# SCH_Badur_Gaddi_v0_1_5.net
KiCad netlist of a schematic drawn in EasyEDA
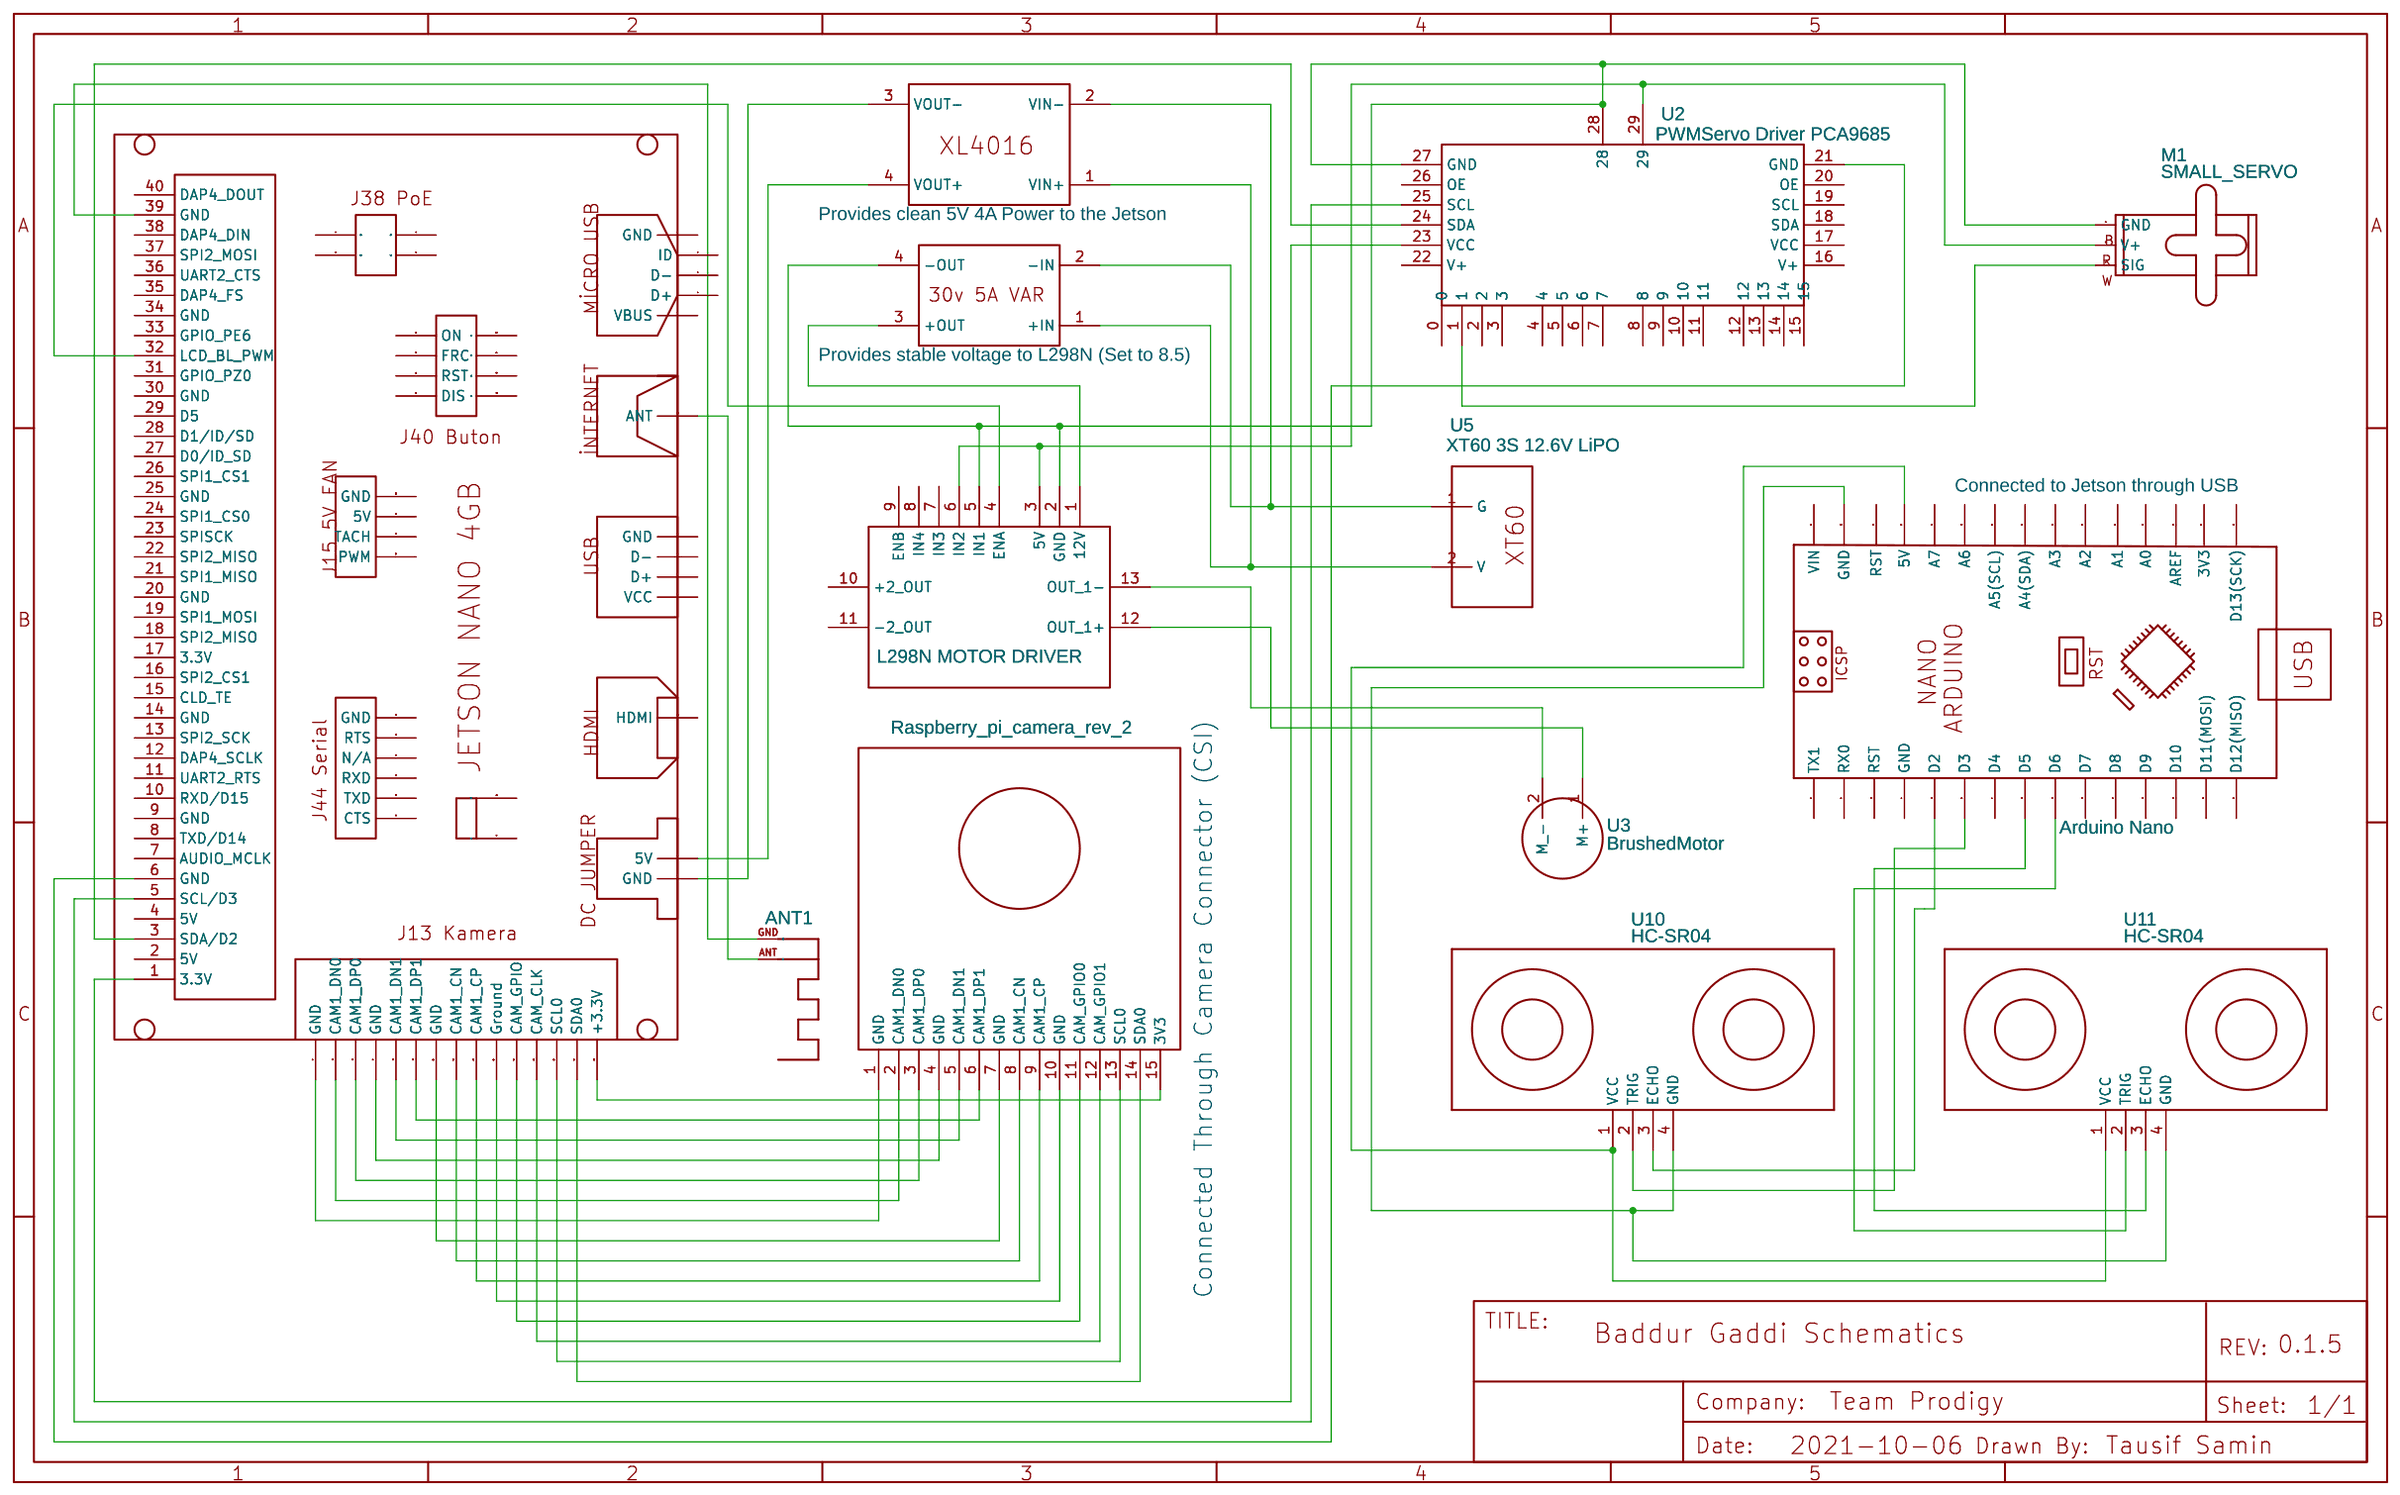
[diagram p0: schematic sheet]

(export (version "E")
  (design (tool "Eeschema 10.0.6"))
  (components
    (comp (ref "ANT1") (value "ANTENNA_WIFI_MIFA") (libsource (lib "") (part "ANTENNA_WIFI_MIFA")))
    (comp (ref "M1") (value "SMALL_SERVO") (libsource (lib "") (part "SMALL_SERVO")))
    (comp (ref "MODULE1") (value "L298N MOTOR DRIVER") (libsource (lib "") (part "L298N MOTOR DRIVER N")))
    (comp (ref "U1") (value "XL4016") (libsource (lib "") (part "XL4016")))
    (comp (ref "U2")
      (value "PWMServo Driver PCA9685")
      (fields
        (field (name "BOM_Manufacturer Part") "815")
        (field (name "BOM_Supplier Part") "16-Channel 12-bit PWMServo Driver PCA9685")
      )
      (libsource (lib "") (part "PWMServo Driver PCA9685"))
    )
    (comp (ref "U3") (value "BrushedMotor") (libsource (lib "") (part "BrushedMotor")))
    (comp (ref "U4") (value "Arduino Nano") (libsource (lib "") (part "Arduino Nano")))
    (comp (ref "U5") (value "XT60 3S 12.6V LiPO") (libsource (lib "") (part "XT60")))
    (comp (ref "U6") (value "jetson nano") (libsource (lib "") (part "jetson nano")))
    (comp (ref "U7")
      (value "Raspberry_pi_camera_rev_2")
      (libsource (lib "") (part "Raspberry_pi_camera_rev_1.3"))
    )
    (comp (ref "U9")
      (value "XL4015 PS 5A")
      (fields (field (name "BOM_Supplier Part") "XL4005"))
      (libsource (lib "") (part "XL4015 PS 5A"))
    )
    (comp (ref "U10") (value "HC-SR04") (libsource (lib "") (part "HC-SR04")))
    (comp (ref "U11") (value "HC-SR04") (libsource (lib "") (part "HC-SR04")))
  )
  (nets
    (net (code "1") (name "Net-(ANT1-PadGND)") (class "Default")
      (node (ref "ANT1") (pin "GND") (pinfunction "GND_GND") (pintype "unspecified"))
      (node (ref "U6") (pin "39") (pinfunction "GND_39") (pintype "unspecified"))
    )
    (net (code "2") (name "Net-(M1-GND)") (class "Default")
      (node (ref "M1") (pin "3") (pinfunction "GND_3") (pintype "unspecified"))
      (node (ref "MODULE1") (pin "2") (pinfunction "GND_2") (pintype "passive"))
      (node (ref "MODULE1") (pin "5") (pinfunction "IN1_5") (pintype "input"))
      (node (ref "U2") (pin "27") (pinfunction "GND_27") (pintype "unspecified"))
      (node (ref "U2") (pin "28") (pinfunction "28_28") (pintype "unspecified"))
      (node (ref "U9") (pin "4") (pinfunction "-OUT_4") (pintype "unspecified"))
    )
    (net (code "3") (name "Net-(M1-SIG)") (class "Default")
      (node (ref "M1") (pin "1") (pinfunction "SIG_1") (pintype "unspecified"))
      (node (ref "U2") (pin "1") (pinfunction "1_1") (pintype "unspecified"))
    )
    (net (code "4") (name "Net-(M1-V+)") (class "Default")
      (node (ref "M1") (pin "2") (pinfunction "V+_2") (pintype "unspecified"))
      (node (ref "MODULE1") (pin "3") (pinfunction "5V_3") (pintype "passive"))
      (node (ref "MODULE1") (pin "6") (pinfunction "IN2_6") (pintype "input"))
      (node (ref "U2") (pin "29") (pinfunction "29_29") (pintype "unspecified"))
    )
    (net (code "5") (name "Net-(MODULE1-12V)") (class "Default")
      (node (ref "MODULE1") (pin "1") (pinfunction "12V_1") (pintype "passive"))
      (node (ref "U9") (pin "3") (pinfunction "+OUT_3") (pintype "unspecified"))
    )
    (net (code "6") (name "Net-(MODULE1-ENA)") (class "Default")
      (node (ref "MODULE1") (pin "4") (pinfunction "ENA_4") (pintype "input"))
      (node (ref "U6") (pin "32") (pinfunction "LCD_BL_PWM_32") (pintype "unspecified"))
    )
    (net (code "7") (name "Net-(MODULE1-OUT_1+)") (class "Default")
      (node (ref "MODULE1") (pin "12") (pinfunction "OUT_1+_12") (pintype "output"))
      (node (ref "U3") (pin "1") (pinfunction "M+_1") (pintype "unspecified"))
    )
    (net (code "8") (name "Net-(MODULE1-OUT_1-)") (class "Default")
      (node (ref "MODULE1") (pin "13") (pinfunction "OUT_1-_13") (pintype "output"))
      (node (ref "U3") (pin "2") (pinfunction "M_-_2") (pintype "unspecified"))
    )
    (net (code "9") (name "Net-(U1-VIN+)") (class "Default")
      (node (ref "U1") (pin "1") (pinfunction "VIN+_1") (pintype "unspecified"))
      (node (ref "U5") (pin "2") (pinfunction "V_2") (pintype "unspecified"))
      (node (ref "U9") (pin "1") (pinfunction "+IN_1") (pintype "unspecified"))
    )
    (net (code "10") (name "Net-(U1-VIN-)") (class "Default")
      (node (ref "U1") (pin "2") (pinfunction "VIN-_2") (pintype "unspecified"))
      (node (ref "U5") (pin "1") (pinfunction "G_1") (pintype "unspecified"))
      (node (ref "U9") (pin "2") (pinfunction "-IN_2") (pintype "unspecified"))
    )
    (net (code "11") (name "Net-(U1-VOUT+)") (class "Default")
      (node (ref "U1") (pin "4") (pinfunction "VOUT+_4") (pintype "unspecified"))
      (node (ref "U6") (pin "62") (pinfunction "5V_62") (pintype "unspecified"))
    )
    (net (code "12") (name "Net-(U1-VOUT-)") (class "Default")
      (node (ref "U1") (pin "3") (pinfunction "VOUT-_3") (pintype "unspecified"))
      (node (ref "U6") (pin "61") (pinfunction "GND_61") (pintype "unspecified"))
    )
    (net (code "13") (name "Net-(U2-GND-Pad21)") (class "Default")
      (node (ref "U2") (pin "21") (pinfunction "GND_21") (pintype "unspecified"))
      (node (ref "U6") (pin "6") (pinfunction "GND_6") (pintype "unspecified"))
    )
    (net (code "14") (name "Net-(U2-VCC-Pad23)") (class "Default")
      (node (ref "U2") (pin "23") (pinfunction "VCC_23") (pintype "unspecified"))
      (node (ref "U6") (pin "1") (pinfunction "3.3V_1") (pintype "unspecified"))
    )
    (net (code "15") (name "Net-(U6-+3.3V)") (class "Default")
      (node (ref "U6") (pin "88") (pinfunction "+3.3V_88") (pintype "unspecified"))
      (node (ref "U7") (pin "15") (pinfunction "3V3_15") (pintype "unspecified"))
    )
    (net (code "16") (name "Net-(U6-ANT)") (class "Default")
      (node (ref "ANT1") (pin "ANT") (pinfunction "ANT_ANT") (pintype "unspecified"))
      (node (ref "U6") (pin "ETHERNET") (pinfunction "ANT_ETHERNET") (pintype "unspecified"))
    )
    (net (code "17") (name "Net-(U6-CAM1_CN)") (class "Default")
      (node (ref "U6") (pin "81") (pinfunction "CAM1_CN_81") (pintype "unspecified"))
      (node (ref "U7") (pin "8") (pinfunction "CAM1_CN_8") (pintype "unspecified"))
    )
    (net (code "18") (name "Net-(U6-CAM1_CP)") (class "Default")
      (node (ref "U6") (pin "82") (pinfunction "CAM1_CP_82") (pintype "unspecified"))
      (node (ref "U7") (pin "9") (pinfunction "CAM1_CP_9") (pintype "unspecified"))
    )
    (net (code "19") (name "Net-(U6-CAM1_DN0)") (class "Default")
      (node (ref "U6") (pin "75") (pinfunction "CAM1_DN0_75") (pintype "unspecified"))
      (node (ref "U7") (pin "2") (pinfunction "CAM1_DN0_2") (pintype "unspecified"))
    )
    (net (code "20") (name "Net-(U6-CAM1_DN1)") (class "Default")
      (node (ref "U6") (pin "78") (pinfunction "CAM1_DN1_78") (pintype "unspecified"))
      (node (ref "U7") (pin "5") (pinfunction "CAM1_DN1_5") (pintype "unspecified"))
    )
    (net (code "21") (name "Net-(U6-CAM1_DP0)") (class "Default")
      (node (ref "U6") (pin "76") (pinfunction "CAM1_DP0_76") (pintype "unspecified"))
      (node (ref "U7") (pin "3") (pinfunction "CAM1_DP0_3") (pintype "unspecified"))
    )
    (net (code "22") (name "Net-(U6-CAM1_DP1)") (class "Default")
      (node (ref "U6") (pin "79") (pinfunction "CAM1_DP1_79") (pintype "unspecified"))
      (node (ref "U7") (pin "6") (pinfunction "CAM1_DP1_6") (pintype "unspecified"))
    )
    (net (code "23") (name "Net-(U6-CAM_CLK)") (class "Default")
      (node (ref "U6") (pin "85") (pinfunction "CAM_CLK_85") (pintype "unspecified"))
      (node (ref "U7") (pin "12") (pinfunction "CAM_GPIO1_12") (pintype "unspecified"))
    )
    (net (code "24") (name "Net-(U6-CAM_GPIO)") (class "Default")
      (node (ref "U6") (pin "84") (pinfunction "CAM_GPIO_84") (pintype "unspecified"))
      (node (ref "U7") (pin "11") (pinfunction "CAM_GPIO0_11") (pintype "unspecified"))
    )
    (net (code "25") (name "Net-(U6-GND-Pad74)") (class "Default")
      (node (ref "U6") (pin "74") (pinfunction "GND_74") (pintype "unspecified"))
      (node (ref "U7") (pin "1") (pinfunction "GND_1") (pintype "unspecified"))
    )
    (net (code "26") (name "Net-(U6-GND-Pad77)") (class "Default")
      (node (ref "U6") (pin "77") (pinfunction "GND_77") (pintype "unspecified"))
      (node (ref "U7") (pin "4") (pinfunction "GND_4") (pintype "unspecified"))
    )
    (net (code "27") (name "Net-(U6-GND-Pad80)") (class "Default")
      (node (ref "U6") (pin "80") (pinfunction "GND_80") (pintype "unspecified"))
      (node (ref "U7") (pin "7") (pinfunction "GND_7") (pintype "unspecified"))
    )
    (net (code "28") (name "Net-(U6-Ground)") (class "Default")
      (node (ref "U6") (pin "83") (pinfunction "Ground_83") (pintype "unspecified"))
      (node (ref "U7") (pin "10") (pinfunction "GND_10") (pintype "unspecified"))
    )
    (net (code "29") (name "Net-(U6-SCL0)") (class "Default")
      (node (ref "U6") (pin "86") (pinfunction "SCL0_86") (pintype "unspecified"))
      (node (ref "U7") (pin "13") (pinfunction "SCL0_13") (pintype "unspecified"))
    )
    (net (code "30") (name "Net-(U6-SCL{slash}D3)") (class "Default")
      (node (ref "U2") (pin "25") (pinfunction "SCL_25") (pintype "unspecified"))
      (node (ref "U6") (pin "5") (pinfunction "SCL/D3_5") (pintype "unspecified"))
    )
    (net (code "31") (name "Net-(U6-SDA0)") (class "Default")
      (node (ref "U6") (pin "87") (pinfunction "SDA0_87") (pintype "unspecified"))
      (node (ref "U7") (pin "14") (pinfunction "SDA0_14") (pintype "unspecified"))
    )
    (net (code "32") (name "Net-(U6-SDA{slash}D2)") (class "Default")
      (node (ref "U2") (pin "24") (pinfunction "SDA_24") (pintype "unspecified"))
      (node (ref "U6") (pin "3") (pinfunction "SDA/D2_3") (pintype "unspecified"))
    )
    (net (code "33") (name "Net-(U10-ECHO)") (class "Default")
      (node (ref "U10") (pin "3") (pinfunction "ECHO_3") (pintype "output"))
      (node (ref "U4") (pin "5") (pinfunction "D2_5") (pintype "unspecified"))
    )
    (net (code "34") (name "Net-(U10-GND)") (class "Default")
      (node (ref "U10") (pin "4") (pinfunction "GND_4") (pintype "passive"))
      (node (ref "U11") (pin "4") (pinfunction "GND_4") (pintype "passive"))
      (node (ref "U4") (pin "29") (pinfunction "GND_29") (pintype "unspecified"))
    )
    (net (code "35") (name "Net-(U10-TRIG)") (class "Default")
      (node (ref "U10") (pin "2") (pinfunction "TRIG_2") (pintype "input"))
      (node (ref "U4") (pin "6") (pinfunction "D3_6") (pintype "unspecified"))
    )
    (net (code "36") (name "Net-(U10-VCC)") (class "Default")
      (node (ref "U10") (pin "1") (pinfunction "VCC_1") (pintype "passive"))
      (node (ref "U11") (pin "1") (pinfunction "VCC_1") (pintype "passive"))
      (node (ref "U4") (pin "27") (pinfunction "5V_27") (pintype "unspecified"))
    )
    (net (code "37") (name "Net-(U11-ECHO)") (class "Default")
      (node (ref "U11") (pin "3") (pinfunction "ECHO_3") (pintype "output"))
      (node (ref "U4") (pin "8") (pinfunction "D5_8") (pintype "unspecified"))
    )
    (net (code "38") (name "Net-(U11-TRIG)") (class "Default")
      (node (ref "U11") (pin "2") (pinfunction "TRIG_2") (pintype "input"))
      (node (ref "U4") (pin "9") (pinfunction "D6_9") (pintype "unspecified"))
    )
    (net (code "39") (name "unconnected-(MODULE1-+2_OUT-Pad10)") (class "Default")
      (node (ref "MODULE1") (pin "10") (pinfunction "+2_OUT_10") (pintype "output"))
    )
    (net (code "40") (name "unconnected-(MODULE1--2_OUT-Pad11)") (class "Default")
      (node (ref "MODULE1") (pin "11") (pinfunction "-2_OUT_11") (pintype "output"))
    )
    (net (code "41") (name "unconnected-(MODULE1-ENB-Pad9)") (class "Default")
      (node (ref "MODULE1") (pin "9") (pinfunction "ENB_9") (pintype "input"))
    )
    (net (code "42") (name "unconnected-(MODULE1-IN3-Pad7)") (class "Default")
      (node (ref "MODULE1") (pin "7") (pinfunction "IN3_7") (pintype "input"))
    )
    (net (code "43") (name "unconnected-(MODULE1-IN4-Pad8)") (class "Default")
      (node (ref "MODULE1") (pin "8") (pinfunction "IN4_8") (pintype "input"))
    )
    (net (code "44") (name "unconnected-(U2-OE-Pad20)") (class "Default")
      (node (ref "U2") (pin "20") (pinfunction "OE_20") (pintype "unspecified"))
    )
    (net (code "45") (name "unconnected-(U2-OE-Pad26)") (class "Default")
      (node (ref "U2") (pin "26") (pinfunction "OE_26") (pintype "unspecified"))
    )
    (net (code "46") (name "unconnected-(U2-Pad0)") (class "Default")
      (node (ref "U2") (pin "0") (pinfunction "0_0") (pintype "unspecified"))
    )
    (net (code "47") (name "unconnected-(U2-Pad2)") (class "Default")
      (node (ref "U2") (pin "2") (pinfunction "2_2") (pintype "unspecified"))
    )
    (net (code "48") (name "unconnected-(U2-Pad3)") (class "Default")
      (node (ref "U2") (pin "3") (pinfunction "3_3") (pintype "unspecified"))
    )
    (net (code "49") (name "unconnected-(U2-Pad4)") (class "Default")
      (node (ref "U2") (pin "4") (pinfunction "4_4") (pintype "unspecified"))
    )
    (net (code "50") (name "unconnected-(U2-Pad5)") (class "Default")
      (node (ref "U2") (pin "5") (pinfunction "5_5") (pintype "unspecified"))
    )
    (net (code "51") (name "unconnected-(U2-Pad6)") (class "Default")
      (node (ref "U2") (pin "6") (pinfunction "6_6") (pintype "unspecified"))
    )
    (net (code "52") (name "unconnected-(U2-Pad7)") (class "Default")
      (node (ref "U2") (pin "7") (pinfunction "7_7") (pintype "unspecified"))
    )
    (net (code "53") (name "unconnected-(U2-Pad8)") (class "Default")
      (node (ref "U2") (pin "8") (pinfunction "8_8") (pintype "unspecified"))
    )
    (net (code "54") (name "unconnected-(U2-Pad9)") (class "Default")
      (node (ref "U2") (pin "9") (pinfunction "9_9") (pintype "unspecified"))
    )
    (net (code "55") (name "unconnected-(U2-Pad10)") (class "Default")
      (node (ref "U2") (pin "10") (pinfunction "10_10") (pintype "unspecified"))
    )
    (net (code "56") (name "unconnected-(U2-Pad11)") (class "Default")
      (node (ref "U2") (pin "11") (pinfunction "11_11") (pintype "unspecified"))
    )
    (net (code "57") (name "unconnected-(U2-Pad12)") (class "Default")
      (node (ref "U2") (pin "12") (pinfunction "12_12") (pintype "unspecified"))
    )
    (net (code "58") (name "unconnected-(U2-Pad13)") (class "Default")
      (node (ref "U2") (pin "13") (pinfunction "13_13") (pintype "unspecified"))
    )
    (net (code "59") (name "unconnected-(U2-Pad14)") (class "Default")
      (node (ref "U2") (pin "14") (pinfunction "14_14") (pintype "unspecified"))
    )
    (net (code "60") (name "unconnected-(U2-Pad15)") (class "Default")
      (node (ref "U2") (pin "15") (pinfunction "15_15") (pintype "unspecified"))
    )
    (net (code "61") (name "unconnected-(U2-SCL-Pad19)") (class "Default")
      (node (ref "U2") (pin "19") (pinfunction "SCL_19") (pintype "unspecified"))
    )
    (net (code "62") (name "unconnected-(U2-SDA-Pad18)") (class "Default")
      (node (ref "U2") (pin "18") (pinfunction "SDA_18") (pintype "unspecified"))
    )
    (net (code "63") (name "unconnected-(U2-V+-Pad16)") (class "Default")
      (node (ref "U2") (pin "16") (pinfunction "V+_16") (pintype "unspecified"))
    )
    (net (code "64") (name "unconnected-(U2-V+-Pad22)") (class "Default")
      (node (ref "U2") (pin "22") (pinfunction "V+_22") (pintype "unspecified"))
    )
    (net (code "65") (name "unconnected-(U2-VCC-Pad17)") (class "Default")
      (node (ref "U2") (pin "17") (pinfunction "VCC_17") (pintype "unspecified"))
    )
    (net (code "66") (name "unconnected-(U4-3V3-Pad17)") (class "Default")
      (node (ref "U4") (pin "17") (pinfunction "3V3_17") (pintype "unspecified"))
    )
    (net (code "67") (name "unconnected-(U4-A0-Pad19)") (class "Default")
      (node (ref "U4") (pin "19") (pinfunction "A0_19") (pintype "unspecified"))
    )
    (net (code "68") (name "unconnected-(U4-A1-Pad20)") (class "Default")
      (node (ref "U4") (pin "20") (pinfunction "A1_20") (pintype "unspecified"))
    )
    (net (code "69") (name "unconnected-(U4-A2-Pad21)") (class "Default")
      (node (ref "U4") (pin "21") (pinfunction "A2_21") (pintype "unspecified"))
    )
    (net (code "70") (name "unconnected-(U4-A3-Pad22)") (class "Default")
      (node (ref "U4") (pin "22") (pinfunction "A3_22") (pintype "unspecified"))
    )
    (net (code "71") (name "unconnected-(U4-A4(SDA)-Pad23)") (class "Default")
      (node (ref "U4") (pin "23") (pinfunction "A4(SDA)_23") (pintype "unspecified"))
    )
    (net (code "72") (name "unconnected-(U4-A5(SCL)-Pad24)") (class "Default")
      (node (ref "U4") (pin "24") (pinfunction "A5(SCL)_24") (pintype "unspecified"))
    )
    (net (code "73") (name "unconnected-(U4-A6-Pad25)") (class "Default")
      (node (ref "U4") (pin "25") (pinfunction "A6_25") (pintype "unspecified"))
    )
    (net (code "74") (name "unconnected-(U4-A7-Pad26)") (class "Default")
      (node (ref "U4") (pin "26") (pinfunction "A7_26") (pintype "unspecified"))
    )
    (net (code "75") (name "unconnected-(U4-AREF-Pad18)") (class "Default")
      (node (ref "U4") (pin "18") (pinfunction "AREF_18") (pintype "unspecified"))
    )
    (net (code "76") (name "unconnected-(U4-D4-Pad7)") (class "Default")
      (node (ref "U4") (pin "7") (pinfunction "D4_7") (pintype "unspecified"))
    )
    (net (code "77") (name "unconnected-(U4-D7-Pad10)") (class "Default")
      (node (ref "U4") (pin "10") (pinfunction "D7_10") (pintype "unspecified"))
    )
    (net (code "78") (name "unconnected-(U4-D8-Pad11)") (class "Default")
      (node (ref "U4") (pin "11") (pinfunction "D8_11") (pintype "unspecified"))
    )
    (net (code "79") (name "unconnected-(U4-D9-Pad12)") (class "Default")
      (node (ref "U4") (pin "12") (pinfunction "D9_12") (pintype "unspecified"))
    )
    (net (code "80") (name "unconnected-(U4-D10-Pad13)") (class "Default")
      (node (ref "U4") (pin "13") (pinfunction "D10_13") (pintype "unspecified"))
    )
    (net (code "81") (name "unconnected-(U4-D11(MOSI)-Pad14)") (class "Default")
      (node (ref "U4") (pin "14") (pinfunction "D11(MOSI)_14") (pintype "unspecified"))
    )
    (net (code "82") (name "unconnected-(U4-D12(MISO)-Pad15)") (class "Default")
      (node (ref "U4") (pin "15") (pinfunction "D12(MISO)_15") (pintype "unspecified"))
    )
    (net (code "83") (name "unconnected-(U4-D13(SCK)-Pad16)") (class "Default")
      (node (ref "U4") (pin "16") (pinfunction "D13(SCK)_16") (pintype "unspecified"))
    )
    (net (code "84") (name "unconnected-(U4-GND-Pad4)") (class "Default")
      (node (ref "U4") (pin "4") (pinfunction "GND_4") (pintype "unspecified"))
    )
    (net (code "85") (name "unconnected-(U4-RST-Pad3)") (class "Default")
      (node (ref "U4") (pin "3") (pinfunction "RST_3") (pintype "unspecified"))
    )
    (net (code "86") (name "unconnected-(U4-RST-Pad28)") (class "Default")
      (node (ref "U4") (pin "28") (pinfunction "RST_28") (pintype "unspecified"))
    )
    (net (code "87") (name "unconnected-(U4-RX0-Pad2)") (class "Default")
      (node (ref "U4") (pin "2") (pinfunction "RX0_2") (pintype "unspecified"))
    )
    (net (code "88") (name "unconnected-(U4-TX1-Pad1)") (class "Default")
      (node (ref "U4") (pin "1") (pinfunction "TX1_1") (pintype "unspecified"))
    )
    (net (code "89") (name "unconnected-(U4-VIN-Pad30)") (class "Default")
      (node (ref "U4") (pin "30") (pinfunction "VIN_30") (pintype "unspecified"))
    )
    (net (code "90") (name "unconnected-(U6-3.3V-Pad17)") (class "Default")
      (node (ref "U6") (pin "17") (pinfunction "3.3V_17") (pintype "unspecified"))
    )
    (net (code "91") (name "unconnected-(U6-5V-Pad2)") (class "Default")
      (node (ref "U6") (pin "2") (pinfunction "5V_2") (pintype "unspecified"))
    )
    (net (code "92") (name "unconnected-(U6-5V-Pad4)") (class "Default")
      (node (ref "U6") (pin "4") (pinfunction "5V_4") (pintype "unspecified"))
    )
    (net (code "93") (name "unconnected-(U6-5V-Pad59)") (class "Default")
      (node (ref "U6") (pin "59") (pinfunction "5V_59") (pintype "unspecified"))
    )
    (net (code "94") (name "unconnected-(U6-AUDIO_MCLK-Pad7)") (class "Default")
      (node (ref "U6") (pin "7") (pinfunction "AUDIO_MCLK_7") (pintype "unspecified"))
    )
    (net (code "95") (name "unconnected-(U6-CLD_TE-Pad15)") (class "Default")
      (node (ref "U6") (pin "15") (pinfunction "CLD_TE_15") (pintype "unspecified"))
    )
    (net (code "96") (name "unconnected-(U6-CTS-Pad41)") (class "Default")
      (node (ref "U6") (pin "41") (pinfunction "CTS_41") (pintype "unspecified"))
    )
    (net (code "97") (name "unconnected-(U6-D+-Pad.)") (class "Default")
      (node (ref "U6") (pin ".") (pinfunction "D+_.") (pintype "unspecified"))
    )
    (net (code "98") (name "unconnected-(U6-D+-Pad71)") (class "Default")
      (node (ref "U6") (pin "71") (pinfunction "D+_71") (pintype "unspecified"))
    )
    (net (code "99") (name "unconnected-(U6-D--Pad.)") (class "Default")
      (node (ref "U6") (pin ".") (pinfunction "D-_.") (pintype "unspecified"))
    )
    (net (code "100") (name "unconnected-(U6-D--Pad72)") (class "Default")
      (node (ref "U6") (pin "72") (pinfunction "D-_72") (pintype "unspecified"))
    )
    (net (code "101") (name "unconnected-(U6-D0{slash}ID_SD-Pad27)") (class "Default")
      (node (ref "U6") (pin "27") (pinfunction "D0/ID_SD_27") (pintype "unspecified"))
    )
    (net (code "102") (name "unconnected-(U6-D1{slash}ID{slash}SD-Pad28)") (class "Default")
      (node (ref "U6") (pin "28") (pinfunction "D1/ID/SD_28") (pintype "unspecified"))
    )
    (net (code "103") (name "unconnected-(U6-D5-Pad29)") (class "Default")
      (node (ref "U6") (pin "29") (pinfunction "D5_29") (pintype "unspecified"))
    )
    (net (code "104") (name "unconnected-(U6-DAP4_DIN-Pad38)") (class "Default")
      (node (ref "U6") (pin "38") (pinfunction "DAP4_DIN_38") (pintype "unspecified"))
    )
    (net (code "105") (name "unconnected-(U6-DAP4_DOUT-Pad40)") (class "Default")
      (node (ref "U6") (pin "40") (pinfunction "DAP4_DOUT_40") (pintype "unspecified"))
    )
    (net (code "106") (name "unconnected-(U6-DAP4_FS-Pad35)") (class "Default")
      (node (ref "U6") (pin "35") (pinfunction "DAP4_FS_35") (pintype "unspecified"))
    )
    (net (code "107") (name "unconnected-(U6-DAP4_SCLK-Pad12)") (class "Default")
      (node (ref "U6") (pin "12") (pinfunction "DAP4_SCLK_12") (pintype "unspecified"))
    )
    (net (code "108") (name "unconnected-(U6-DIS-Pad56)") (class "Default")
      (node (ref "U6") (pin "56") (pinfunction "DIS_56") (pintype "unspecified"))
    )
    (net (code "109") (name "unconnected-(U6-FRC-Pad54)") (class "Default")
      (node (ref "U6") (pin "54") (pinfunction "FRC_54") (pintype "unspecified"))
    )
    (net (code "110") (name "unconnected-(U6-GND-Pad.)") (class "Default")
      (node (ref "U6") (pin ".") (pinfunction "GND_.") (pintype "unspecified"))
    )
    (net (code "111") (name "unconnected-(U6-GND-Pad.)_1") (class "Default")
      (node (ref "U6") (pin ".") (pinfunction "GND_.") (pintype "unspecified"))
    )
    (net (code "112") (name "unconnected-(U6-GND-Pad.)_2") (class "Default")
      (node (ref "U6") (pin ".") (pinfunction "GND_.") (pintype "unspecified"))
    )
    (net (code "113") (name "unconnected-(U6-GND-Pad.)_3") (class "Default")
      (node (ref "U6") (pin ".") (pinfunction "GND_.") (pintype "unspecified"))
    )
    (net (code "114") (name "unconnected-(U6-GND-Pad.)_4") (class "Default")
      (node (ref "U6") (pin ".") (pinfunction "GND_.") (pintype "unspecified"))
    )
    (net (code "115") (name "unconnected-(U6-GND-Pad9)") (class "Default")
      (node (ref "U6") (pin "9") (pinfunction "GND_9") (pintype "unspecified"))
    )
    (net (code "116") (name "unconnected-(U6-GND-Pad14)") (class "Default")
      (node (ref "U6") (pin "14") (pinfunction "GND_14") (pintype "unspecified"))
    )
    (net (code "117") (name "unconnected-(U6-GND-Pad20)") (class "Default")
      (node (ref "U6") (pin "20") (pinfunction "GND_20") (pintype "unspecified"))
    )
    (net (code "118") (name "unconnected-(U6-GND-Pad25)") (class "Default")
      (node (ref "U6") (pin "25") (pinfunction "GND_25") (pintype "unspecified"))
    )
    (net (code "119") (name "unconnected-(U6-GND-Pad30)") (class "Default")
      (node (ref "U6") (pin "30") (pinfunction "GND_30") (pintype "unspecified"))
    )
    (net (code "120") (name "unconnected-(U6-GND-Pad34)") (class "Default")
      (node (ref "U6") (pin "34") (pinfunction "GND_34") (pintype "unspecified"))
    )
    (net (code "121") (name "unconnected-(U6-GND-Pad46)") (class "Default")
      (node (ref "U6") (pin "46") (pinfunction "GND_46") (pintype "unspecified"))
    )
    (net (code "122") (name "unconnected-(U6-GND-Pad60)") (class "Default")
      (node (ref "U6") (pin "60") (pinfunction "GND_60") (pintype "unspecified"))
    )
    (net (code "123") (name "unconnected-(U6-GND-Pad73)") (class "Default")
      (node (ref "U6") (pin "73") (pinfunction "GND_73") (pintype "unspecified"))
    )
    (net (code "124") (name "unconnected-(U6-GPIO_PE6-Pad33)") (class "Default")
      (node (ref "U6") (pin "33") (pinfunction "GPIO_PE6_33") (pintype "unspecified"))
    )
    (net (code "125") (name "unconnected-(U6-GPIO_PZ0-Pad31)") (class "Default")
      (node (ref "U6") (pin "31") (pinfunction "GPIO_PZ0_31") (pintype "unspecified"))
    )
    (net (code "126") (name "unconnected-(U6-HDMI-PadETHERNET)") (class "Default")
      (node (ref "U6") (pin "ETHERNET") (pinfunction "HDMI_ETHERNET") (pintype "unspecified"))
    )
    (net (code "127") (name "unconnected-(U6-ID-Pad.)") (class "Default")
      (node (ref "U6") (pin ".") (pinfunction "ID_.") (pintype "unspecified"))
    )
    (net (code "128") (name "unconnected-(U6-N{slash}A-Pad44)") (class "Default")
      (node (ref "U6") (pin "44") (pinfunction "N/A_44") (pintype "unspecified"))
    )
    (net (code "129") (name "unconnected-(U6-ON-Pad53)") (class "Default")
      (node (ref "U6") (pin "53") (pinfunction "ON_53") (pintype "unspecified"))
    )
    (net (code "130") (name "unconnected-(U6-PWM-Pad57)") (class "Default")
      (node (ref "U6") (pin "57") (pinfunction "PWM_57") (pintype "unspecified"))
    )
    (net (code "131") (name "unconnected-(U6-Pad47)") (class "Default")
      (node (ref "U6") (pin "47") (pinfunction "47_47") (pintype "unspecified"))
    )
    (net (code "132") (name "unconnected-(U6-Pad48)") (class "Default")
      (node (ref "U6") (pin "48") (pinfunction "48_48") (pintype "unspecified"))
    )
    (net (code "133") (name "unconnected-(U6-Pad49)") (class "Default")
      (node (ref "U6") (pin "49") (pinfunction "49_49") (pintype "unspecified"))
    )
    (net (code "134") (name "unconnected-(U6-Pad50)") (class "Default")
      (node (ref "U6") (pin "50") (pinfunction "50_50") (pintype "unspecified"))
    )
    (net (code "135") (name "unconnected-(U6-Pad51)") (class "Default")
      (node (ref "U6") (pin "51") (pinfunction "51_51") (pintype "unspecified"))
    )
    (net (code "136") (name "unconnected-(U6-Pad52)") (class "Default")
      (node (ref "U6") (pin "52") (pinfunction "52_52") (pintype "unspecified"))
    )
    (net (code "137") (name "unconnected-(U6-RST-Pad55)") (class "Default")
      (node (ref "U6") (pin "55") (pinfunction "RST_55") (pintype "unspecified"))
    )
    (net (code "138") (name "unconnected-(U6-RTS-Pad45)") (class "Default")
      (node (ref "U6") (pin "45") (pinfunction "RTS_45") (pintype "unspecified"))
    )
    (net (code "139") (name "unconnected-(U6-RXD-Pad43)") (class "Default")
      (node (ref "U6") (pin "43") (pinfunction "RXD_43") (pintype "unspecified"))
    )
    (net (code "140") (name "unconnected-(U6-RXD{slash}D15-Pad10)") (class "Default")
      (node (ref "U6") (pin "10") (pinfunction "RXD/D15_10") (pintype "unspecified"))
    )
    (net (code "141") (name "unconnected-(U6-SPI1_CS0-Pad24)") (class "Default")
      (node (ref "U6") (pin "24") (pinfunction "SPI1_CS0_24") (pintype "unspecified"))
    )
    (net (code "142") (name "unconnected-(U6-SPI1_CS1-Pad26)") (class "Default")
      (node (ref "U6") (pin "26") (pinfunction "SPI1_CS1_26") (pintype "unspecified"))
    )
    (net (code "143") (name "unconnected-(U6-SPI1_MISO-Pad21)") (class "Default")
      (node (ref "U6") (pin "21") (pinfunction "SPI1_MISO_21") (pintype "unspecified"))
    )
    (net (code "144") (name "unconnected-(U6-SPI1_MOSI-Pad19)") (class "Default")
      (node (ref "U6") (pin "19") (pinfunction "SPI1_MOSI_19") (pintype "unspecified"))
    )
    (net (code "145") (name "unconnected-(U6-SPI2_CS1-Pad16)") (class "Default")
      (node (ref "U6") (pin "16") (pinfunction "SPI2_CS1_16") (pintype "unspecified"))
    )
    (net (code "146") (name "unconnected-(U6-SPI2_MISO-Pad18)") (class "Default")
      (node (ref "U6") (pin "18") (pinfunction "SPI2_MISO_18") (pintype "unspecified"))
    )
    (net (code "147") (name "unconnected-(U6-SPI2_MISO-Pad22)") (class "Default")
      (node (ref "U6") (pin "22") (pinfunction "SPI2_MISO_22") (pintype "unspecified"))
    )
    (net (code "148") (name "unconnected-(U6-SPI2_MOSI-Pad37)") (class "Default")
      (node (ref "U6") (pin "37") (pinfunction "SPI2_MOSI_37") (pintype "unspecified"))
    )
    (net (code "149") (name "unconnected-(U6-SPI2_SCK-Pad13)") (class "Default")
      (node (ref "U6") (pin "13") (pinfunction "SPI2_SCK_13") (pintype "unspecified"))
    )
    (net (code "150") (name "unconnected-(U6-SPISCK-Pad23)") (class "Default")
      (node (ref "U6") (pin "23") (pinfunction "SPISCK_23") (pintype "unspecified"))
    )
    (net (code "151") (name "unconnected-(U6-TACH-Pad58)") (class "Default")
      (node (ref "U6") (pin "58") (pinfunction "TACH_58") (pintype "unspecified"))
    )
    (net (code "152") (name "unconnected-(U6-TXD-Pad42)") (class "Default")
      (node (ref "U6") (pin "42") (pinfunction "TXD_42") (pintype "unspecified"))
    )
    (net (code "153") (name "unconnected-(U6-TXD{slash}D14-Pad8)") (class "Default")
      (node (ref "U6") (pin "8") (pinfunction "TXD/D14_8") (pintype "unspecified"))
    )
    (net (code "154") (name "unconnected-(U6-UART2_CTS-Pad36)") (class "Default")
      (node (ref "U6") (pin "36") (pinfunction "UART2_CTS_36") (pintype "unspecified"))
    )
    (net (code "155") (name "unconnected-(U6-UART2_RTS-Pad11)") (class "Default")
      (node (ref "U6") (pin "11") (pinfunction "UART2_RTS_11") (pintype "unspecified"))
    )
    (net (code "156") (name "unconnected-(U6-VBUS-Pad.)") (class "Default")
      (node (ref "U6") (pin ".") (pinfunction "VBUS_.") (pintype "unspecified"))
    )
    (net (code "157") (name "unconnected-(U6-VCC-Pad70)") (class "Default")
      (node (ref "U6") (pin "70") (pinfunction "VCC_70") (pintype "unspecified"))
    )
  )
)
